# Nico_Microcontroller.net
KiCad netlist of a schematic drawn in EAGLE
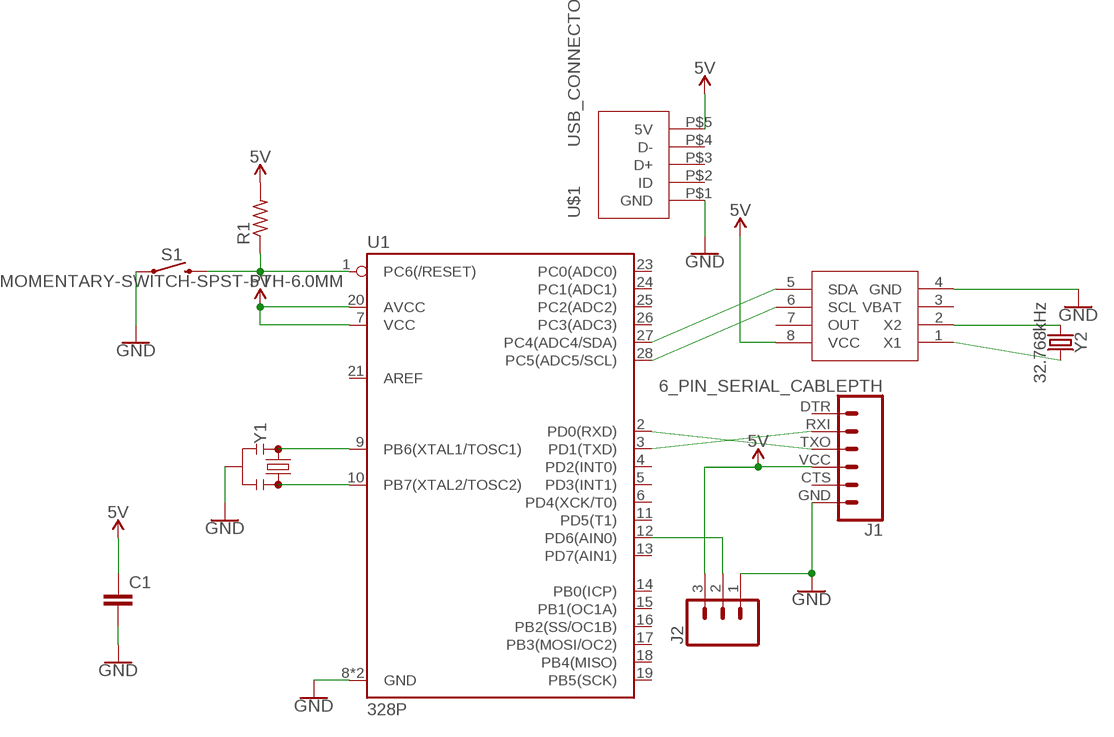
[diagram p0: schematic, sheet 1]

(export (version "E")
  (design (tool "Eeschema 10.0.6"))
  (components
    (comp (ref "C1")
      (value "C2.5/2")
      (footprint "eagle-import:C2.5-2")
      (libsource (lib "eagle-import") (part "C2.5/2"))
    )
    (comp (ref "J1")
      (value "6_PIN_SERIAL_CABLEPTH")
      (footprint "eagle-import:FTDI_BASIC")
      (libsource (lib "eagle-import") (part "6_PIN_SERIAL_CABLEPTH"))
    )
    (comp (ref "J2")
      (value "CONN_03")
      (footprint "eagle-import:1X03")
      (libsource (lib "eagle-import") (part "CONN_03"))
    )
    (comp (ref "R1")
      (value "R-US_0204/5")
      (footprint "eagle-import:0204_5")
      (libsource (lib "eagle-import") (part "R-US_0204/5"))
    )
    (comp (ref "S1")
      (value "MOMENTARY-SWITCH-SPST-PTH-6.0MM")
      (footprint "eagle-import:TACTILE_SWITCH_PTH_6.0MM")
      (libsource (lib "eagle-import") (part "MOMENTARY-SWITCH-SPST-PTH-6.0MM"))
    )
    (comp (ref "U$1")
      (value "USB_CONNECTOR")
      (footprint "eagle-import:USB-CONNECTOR")
      (libsource (lib "eagle-import") (part "USB_CONNECTOR"))
    )
    (comp (ref "U$2")
      (value "DS1307")
      (footprint "eagle-import:DIP08")
      (libsource (lib "eagle-import") (part "DS1307"))
    )
    (comp (ref "U1")
      (value "328P")
      (footprint "eagle-import:DIP28")
      (libsource (lib "eagle-import") (part "ATMEGA328P_PDIP"))
    )
    (comp (ref "Y1")
      (value "RESONATORPTH-7.6X3.8")
      (footprint "eagle-import:RESONATOR-PTH-7.6X3.8")
      (libsource (lib "eagle-import") (part "RESONATORPTH-7.6X3.8"))
    )
    (comp (ref "Y2")
      (value "32.768kHz")
      (footprint "eagle-import:CRYSTAL-PTH-2X6-CYL")
      (libsource (lib "eagle-import") (part "CRYSTAL-32.768KHZPTH-2X6"))
    )
  )
  (nets
    (net (code "1") (name "5V") (class "Default")
      (node (ref "C1") (pin "1") (pinfunction "1_1") (pintype "passive"))
      (node (ref "J1") (pin "VCC") (pinfunction "4_VCC") (pintype "passive"))
      (node (ref "J2") (pin "3") (pinfunction "3_3") (pintype "passive"))
      (node (ref "R1") (pin "2") (pinfunction "2_2") (pintype "passive"))
      (node (ref "U$1") (pin "P$5") (pinfunction "5V_P$5") (pintype "bidirectional"))
      (node (ref "U$2") (pin "8") (pinfunction "VCC_8") (pintype "bidirectional"))
      (node (ref "U1") (pin "20") (pinfunction "AVCC_20") (pintype "bidirectional"))
      (node (ref "U1") (pin "7") (pinfunction "VCC_7") (pintype "bidirectional"))
    )
    (net (code "2") (name "GND") (class "Default")
      (node (ref "C1") (pin "2") (pinfunction "2_2") (pintype "passive"))
      (node (ref "J1") (pin "GND") (pinfunction "6_GND") (pintype "passive"))
      (node (ref "J2") (pin "1") (pinfunction "1_1") (pintype "passive"))
      (node (ref "S1") (pin "1") (pinfunction "1_1") (pintype "passive"))
      (node (ref "U$1") (pin "P$1") (pinfunction "GND_P$1") (pintype "bidirectional"))
      (node (ref "U$2") (pin "4") (pinfunction "GND_4") (pintype "bidirectional"))
      (node (ref "U1") (pin "22") (pinfunction "GND_22") (pintype "bidirectional"))
      (node (ref "U1") (pin "8") (pinfunction "GND_8") (pintype "bidirectional"))
      (node (ref "Y1") (pin "2") (pinfunction "2_2") (pintype "passive"))
    )
    (net (code "3") (name "Net-(J1-2)") (class "Default")
      (node (ref "J1") (pin "RXI") (pinfunction "2_RXI") (pintype "passive"))
      (node (ref "U1") (pin "3") (pinfunction "PD1(TXD)_3") (pintype "bidirectional"))
    )
    (net (code "4") (name "Net-(J1-3)") (class "Default")
      (node (ref "J1") (pin "TXO") (pinfunction "3_TXO") (pintype "passive"))
      (node (ref "U1") (pin "2") (pinfunction "PD0(RXD)_2") (pintype "bidirectional"))
    )
    (net (code "5") (name "Net-(S1-2)") (class "Default")
      (node (ref "R1") (pin "1") (pinfunction "1_1") (pintype "passive"))
      (node (ref "S1") (pin "3") (pinfunction "2_3") (pintype "passive"))
      (node (ref "U1") (pin "1") (pinfunction "PC6(/RESET)_1") (pintype "bidirectional"))
    )
    (net (code "6") (name "Net-(U$2-SCL)") (class "Default")
      (node (ref "U$2") (pin "6") (pinfunction "SCL_6") (pintype "bidirectional"))
      (node (ref "U1") (pin "28") (pinfunction "PC5(ADC5/SCL)_28") (pintype "bidirectional"))
    )
    (net (code "7") (name "Net-(U$2-SDA)") (class "Default")
      (node (ref "U$2") (pin "5") (pinfunction "SDA_5") (pintype "bidirectional"))
      (node (ref "U1") (pin "27") (pinfunction "PC4(ADC4/SDA)_27") (pintype "bidirectional"))
    )
    (net (code "8") (name "Net-(U$2-X1)") (class "Default")
      (node (ref "U$2") (pin "1") (pinfunction "X1_1") (pintype "bidirectional"))
      (node (ref "Y2") (pin "2") (pinfunction "2_2") (pintype "passive"))
    )
    (net (code "9") (name "Net-(U$2-X2)") (class "Default")
      (node (ref "U$2") (pin "2") (pinfunction "X2_2") (pintype "bidirectional"))
      (node (ref "Y2") (pin "1") (pinfunction "1_1") (pintype "passive"))
    )
    (net (code "10") (name "Net-(U1-PB6(XTAL1{slash}TOSC1))") (class "Default")
      (node (ref "U1") (pin "9") (pinfunction "PB6(XTAL1/TOSC1)_9") (pintype "bidirectional"))
      (node (ref "Y1") (pin "1") (pinfunction "1_1") (pintype "passive"))
    )
    (net (code "11") (name "Net-(U1-PB7(XTAL2{slash}TOSC2))") (class "Default")
      (node (ref "U1") (pin "10") (pinfunction "PB7(XTAL2/TOSC2)_10") (pintype "bidirectional"))
      (node (ref "Y1") (pin "3") (pinfunction "3_3") (pintype "passive"))
    )
    (net (code "12") (name "Net-(U1-PD6(AIN0))") (class "Default")
      (node (ref "J2") (pin "2") (pinfunction "2_2") (pintype "passive"))
      (node (ref "U1") (pin "12") (pinfunction "PD6(AIN0)_12") (pintype "bidirectional"))
    )
    (net (code "13") (name "unconnected-(J1-1-PadDTR)") (class "Default")
      (node (ref "J1") (pin "DTR") (pinfunction "1_DTR") (pintype "passive"))
    )
    (net (code "14") (name "unconnected-(J1-5-PadCTS)") (class "Default")
      (node (ref "J1") (pin "CTS") (pinfunction "5_CTS") (pintype "passive"))
    )
    (net (code "15") (name "unconnected-(U$1-D+-PadP$3)") (class "Default")
      (node (ref "U$1") (pin "P$3") (pinfunction "D+_P$3") (pintype "bidirectional"))
    )
    (net (code "16") (name "unconnected-(U$1-D--PadP$4)") (class "Default")
      (node (ref "U$1") (pin "P$4") (pinfunction "D-_P$4") (pintype "bidirectional"))
    )
    (net (code "17") (name "unconnected-(U$1-ID-PadP$2)") (class "Default")
      (node (ref "U$1") (pin "P$2") (pinfunction "ID_P$2") (pintype "bidirectional"))
    )
    (net (code "18") (name "unconnected-(U$2-OUT-Pad7)") (class "Default")
      (node (ref "U$2") (pin "7") (pinfunction "OUT_7") (pintype "bidirectional"))
    )
    (net (code "19") (name "unconnected-(U$2-VBAT-Pad3)") (class "Default")
      (node (ref "U$2") (pin "3") (pinfunction "VBAT_3") (pintype "bidirectional"))
    )
    (net (code "20") (name "unconnected-(U1-AREF-Pad21)") (class "Default")
      (node (ref "U1") (pin "21") (pinfunction "AREF_21") (pintype "bidirectional"))
    )
    (net (code "21") (name "unconnected-(U1-PB0(ICP)-Pad14)") (class "Default")
      (node (ref "U1") (pin "14") (pinfunction "PB0(ICP)_14") (pintype "bidirectional"))
    )
    (net (code "22") (name "unconnected-(U1-PB1(OC1A)-Pad15)") (class "Default")
      (node (ref "U1") (pin "15") (pinfunction "PB1(OC1A)_15") (pintype "bidirectional"))
    )
    (net (code "23") (name "unconnected-(U1-PB2(SS{slash}OC1B)-Pad16)") (class "Default")
      (node (ref "U1") (pin "16") (pinfunction "PB2(SS/OC1B)_16") (pintype "bidirectional"))
    )
    (net (code "24") (name "unconnected-(U1-PB3(MOSI{slash}OC2)-Pad17)") (class "Default")
      (node (ref "U1") (pin "17") (pinfunction "PB3(MOSI/OC2)_17") (pintype "bidirectional"))
    )
    (net (code "25") (name "unconnected-(U1-PB4(MISO)-Pad18)") (class "Default")
      (node (ref "U1") (pin "18") (pinfunction "PB4(MISO)_18") (pintype "bidirectional"))
    )
    (net (code "26") (name "unconnected-(U1-PB5(SCK)-Pad19)") (class "Default")
      (node (ref "U1") (pin "19") (pinfunction "PB5(SCK)_19") (pintype "bidirectional"))
    )
    (net (code "27") (name "unconnected-(U1-PC0(ADC0)-Pad23)") (class "Default")
      (node (ref "U1") (pin "23") (pinfunction "PC0(ADC0)_23") (pintype "bidirectional"))
    )
    (net (code "28") (name "unconnected-(U1-PC1(ADC1)-Pad24)") (class "Default")
      (node (ref "U1") (pin "24") (pinfunction "PC1(ADC1)_24") (pintype "bidirectional"))
    )
    (net (code "29") (name "unconnected-(U1-PC2(ADC2)-Pad25)") (class "Default")
      (node (ref "U1") (pin "25") (pinfunction "PC2(ADC2)_25") (pintype "bidirectional"))
    )
    (net (code "30") (name "unconnected-(U1-PC3(ADC3)-Pad26)") (class "Default")
      (node (ref "U1") (pin "26") (pinfunction "PC3(ADC3)_26") (pintype "bidirectional"))
    )
    (net (code "31") (name "unconnected-(U1-PD2(INT0)-Pad4)") (class "Default")
      (node (ref "U1") (pin "4") (pinfunction "PD2(INT0)_4") (pintype "bidirectional"))
    )
    (net (code "32") (name "unconnected-(U1-PD3(INT1)-Pad5)") (class "Default")
      (node (ref "U1") (pin "5") (pinfunction "PD3(INT1)_5") (pintype "bidirectional"))
    )
    (net (code "33") (name "unconnected-(U1-PD4(XCK{slash}T0)-Pad6)") (class "Default")
      (node (ref "U1") (pin "6") (pinfunction "PD4(XCK/T0)_6") (pintype "bidirectional"))
    )
    (net (code "34") (name "unconnected-(U1-PD5(T1)-Pad11)") (class "Default")
      (node (ref "U1") (pin "11") (pinfunction "PD5(T1)_11") (pintype "bidirectional"))
    )
    (net (code "35") (name "unconnected-(U1-PD7(AIN1)-Pad13)") (class "Default")
      (node (ref "U1") (pin "13") (pinfunction "PD7(AIN1)_13") (pintype "bidirectional"))
    )
  )
)
